# usbFilter.net
KiCad netlist of a schematic drawn in EAGLE
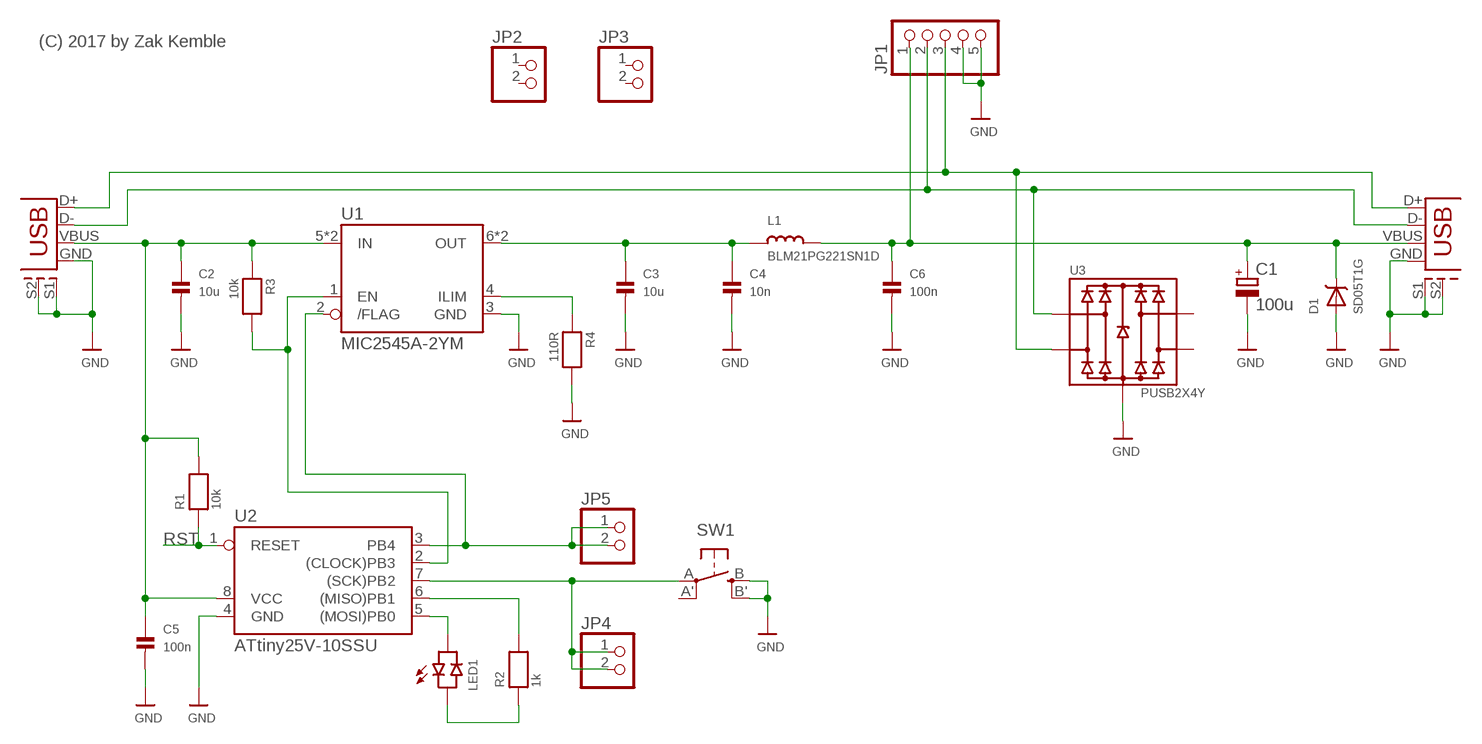
[diagram p0: schematic, sheet 1]

(export (version "E")
  (design (tool "Eeschema 10.0.6"))
  (components
    (comp (ref "C1")
      (value "100u")
      (footprint "eagle-import:E2,5-6")
      (libsource (lib "eagle-import") (part "CPOL-EUE2.5-6"))
    )
    (comp (ref "C2")
      (value "10u")
      (footprint "eagle-import:0805_NO_OUTLINE")
      (libsource (lib "eagle-import") (part "CAP_CERAMIC0805"))
    )
    (comp (ref "C3")
      (value "10u")
      (footprint "eagle-import:0805_NO_OUTLINE")
      (libsource (lib "eagle-import") (part "CAP_CERAMIC0805"))
    )
    (comp (ref "C4")
      (value "10n")
      (footprint "eagle-import:0402")
      (libsource (lib "eagle-import") (part "CAP_CERAMIC0402"))
    )
    (comp (ref "C5")
      (value "100n")
      (footprint "eagle-import:0402")
      (libsource (lib "eagle-import") (part "CAP_CERAMIC0402"))
    )
    (comp (ref "C6")
      (value "100n")
      (footprint "eagle-import:0402")
      (libsource (lib "eagle-import") (part "CAP_CERAMIC0402"))
    )
    (comp (ref "D1")
      (value "SD05T1G")
      (footprint "eagle-import:SOD-323")
      (libsource (lib "eagle-import") (part "DIODE-ZENERSOD-323"))
    )
    (comp (ref "JP1")
      (value "PINHD-1X5")
      (footprint "eagle-import:1X05")
      (libsource (lib "eagle-import") (part "PINHD-1X5"))
    )
    (comp (ref "JP2")
      (value "PINHD-1X2")
      (footprint "eagle-import:1X02")
      (libsource (lib "eagle-import") (part "PINHD-1X2"))
    )
    (comp (ref "JP3")
      (value "PINHD-1X2")
      (footprint "eagle-import:1X02")
      (libsource (lib "eagle-import") (part "PINHD-1X2"))
    )
    (comp (ref "JP4")
      (value "PINHD-1X2")
      (footprint "eagle-import:1X02")
      (libsource (lib "eagle-import") (part "PINHD-1X2"))
    )
    (comp (ref "JP5")
      (value "PINHD-1X2")
      (footprint "eagle-import:1X02")
      (libsource (lib "eagle-import") (part "PINHD-1X2"))
    )
    (comp (ref "L1")
      (value "BLM21PG221SN1D")
      (footprint "eagle-import:0805_NO_OUTLINE")
      (libsource (lib "eagle-import") (part "INDUCTOR0805"))
    )
    (comp (ref "LED1")
      (value "LEDBI0805")
      (footprint "eagle-import:CHIPLED_0805_NOOUTLINE")
      (libsource (lib "eagle-import") (part "LEDBI0805"))
    )
    (comp (ref "R1")
      (value "10k")
      (footprint "eagle-import:0402")
      (libsource (lib "eagle-import") (part "RESISTOR0402"))
    )
    (comp (ref "R2")
      (value "1k")
      (footprint "eagle-import:0402")
      (libsource (lib "eagle-import") (part "RESISTOR0402"))
    )
    (comp (ref "R3")
      (value "10k")
      (footprint "eagle-import:0402")
      (libsource (lib "eagle-import") (part "RESISTOR0402"))
    )
    (comp (ref "R4")
      (value "110R")
      (footprint "eagle-import:0805_NO_OUTLINE")
      (libsource (lib "eagle-import") (part "RESISTOR0805_NO_OUTLINE"))
    )
    (comp (ref "SW1")
      (value "SPST_TACTMC32882")
      (footprint "eagle-import:TACT_SMD4")
      (libsource (lib "eagle-import") (part "SPST_TACTMC32882"))
    )
    (comp (ref "U1")
      (value "MIC2545A-2YM")
      (footprint "eagle-import:SOIC8_150MIL_SMPAD")
      (libsource (lib "eagle-import") (part "NCP380MIC2545"))
    )
    (comp (ref "U2")
      (value "ATtiny25V-10SSU")
      (footprint "eagle-import:SOIC8_150MIL_SMPAD")
      (libsource (lib "eagle-import") (part "ATTINY85150MIL_SMPAD"))
    )
    (comp (ref "U3")
      (value "PUSB2X4Y")
      (footprint "eagle-import:SOT-363")
      (libsource (lib "eagle-import") (part "PUSB2X4Y"))
    )
    (comp (ref "USB1")
      (value "USB-TYPE-B")
      (footprint "eagle-import:USB-TYPE-B")
      (libsource (lib "eagle-import") (part "USB-TYPE-B"))
    )
    (comp (ref "USB2")
      (value "USB-TYPE-A-VERT")
      (footprint "eagle-import:USB-TYPE-A-VERT")
      (libsource (lib "eagle-import") (part "USB-TYPE-A-VERT"))
    )
  )
  (nets
    (net (code "1") (name "/RST") (class "Default")
      (node (ref "R1") (pin "1") (pinfunction "1_1") (pintype "passive"))
      (node (ref "U2") (pin "1") (pinfunction "RESET_1") (pintype "input"))
    )
    (net (code "2") (name "GND") (class "Default")
      (node (ref "C1") (pin "-") (pinfunction "-_-") (pintype "passive"))
      (node (ref "C2") (pin "2") (pinfunction "P$2_2") (pintype "passive"))
      (node (ref "C3") (pin "2") (pinfunction "P$2_2") (pintype "passive"))
      (node (ref "C4") (pin "2") (pinfunction "P$2_2") (pintype "passive"))
      (node (ref "C5") (pin "2") (pinfunction "P$2_2") (pintype "passive"))
      (node (ref "C6") (pin "2") (pinfunction "P$2_2") (pintype "passive"))
      (node (ref "D1") (pin "A") (pinfunction "A_A") (pintype "passive"))
      (node (ref "JP1") (pin "4") (pinfunction "4_4") (pintype "passive"))
      (node (ref "JP1") (pin "5") (pinfunction "5_5") (pintype "passive"))
      (node (ref "R4") (pin "2") (pinfunction "2_2") (pintype "passive"))
      (node (ref "SW1") (pin "B") (pinfunction "S_B") (pintype "passive"))
      (node (ref "SW1") (pin "B'") (pinfunction "S1_B'") (pintype "passive"))
      (node (ref "U1") (pin "3") (pinfunction "GND_3") (pintype "passive"))
      (node (ref "U2") (pin "4") (pinfunction "GND_4") (pintype "power_in"))
      (node (ref "U3") (pin "2") (pinfunction "GND_2") (pintype "passive"))
      (node (ref "USB1") (pin "GND") (pinfunction "GND_GND") (pintype "bidirectional"))
      (node (ref "USB1") (pin "S1") (pinfunction "SHEILD1_S1") (pintype "bidirectional"))
      (node (ref "USB1") (pin "S2") (pinfunction "SHEILD2_S2") (pintype "bidirectional"))
      (node (ref "USB2") (pin "GND") (pinfunction "GND_GND") (pintype "bidirectional"))
      (node (ref "USB2") (pin "S1") (pinfunction "SHEILD1_S1") (pintype "bidirectional"))
      (node (ref "USB2") (pin "S2") (pinfunction "SHEILD2_S2") (pintype "bidirectional"))
    )
    (net (code "3") (name "Net-(C2-P$1)") (class "Default")
      (node (ref "C2") (pin "1") (pinfunction "P$1_1") (pintype "passive"))
      (node (ref "C5") (pin "1") (pinfunction "P$1_1") (pintype "passive"))
      (node (ref "R1") (pin "2") (pinfunction "2_2") (pintype "passive"))
      (node (ref "R3") (pin "1") (pinfunction "1_1") (pintype "passive"))
      (node (ref "U1") (pin "5") (pinfunction "IN_5") (pintype "passive"))
      (node (ref "U1") (pin "7") (pinfunction "IN_7") (pintype "passive"))
      (node (ref "U2") (pin "8") (pinfunction "VCC_8") (pintype "power_in"))
      (node (ref "USB1") (pin "VBUS") (pinfunction "VBUS_VBUS") (pintype "bidirectional"))
    )
    (net (code "4") (name "Net-(C3-P$1)") (class "Default")
      (node (ref "C3") (pin "1") (pinfunction "P$1_1") (pintype "passive"))
      (node (ref "C4") (pin "1") (pinfunction "P$1_1") (pintype "passive"))
      (node (ref "L1") (pin "1") (pinfunction "1_1") (pintype "passive"))
      (node (ref "U1") (pin "6") (pinfunction "OUT_6") (pintype "passive"))
      (node (ref "U1") (pin "8") (pinfunction "OUT_8") (pintype "passive"))
    )
    (net (code "5") (name "Net-(C6-P$1)") (class "Default")
      (node (ref "C1") (pin "+") (pinfunction "+_+") (pintype "passive"))
      (node (ref "C6") (pin "1") (pinfunction "P$1_1") (pintype "passive"))
      (node (ref "D1") (pin "C") (pinfunction "C_C") (pintype "passive"))
      (node (ref "JP1") (pin "1") (pinfunction "1_1") (pintype "passive"))
      (node (ref "L1") (pin "2") (pinfunction "2_2") (pintype "passive"))
      (node (ref "USB2") (pin "VBUS") (pinfunction "VBUS_VBUS") (pintype "bidirectional"))
    )
    (net (code "6") (name "Net-(LED1-PadC)") (class "Default")
      (node (ref "LED1") (pin "C") (pinfunction "C_C") (pintype "passive"))
      (node (ref "R2") (pin "1") (pinfunction "1_1") (pintype "passive"))
    )
    (net (code "7") (name "Net-(SW1-P)") (class "Default")
      (node (ref "JP4") (pin "1") (pinfunction "1_1") (pintype "passive"))
      (node (ref "JP4") (pin "2") (pinfunction "2_2") (pintype "passive"))
      (node (ref "SW1") (pin "A") (pinfunction "P_A") (pintype "passive"))
      (node (ref "U2") (pin "7") (pinfunction "(SCK)PB2_7") (pintype "bidirectional"))
    )
    (net (code "8") (name "Net-(U1-EN)") (class "Default")
      (node (ref "R3") (pin "2") (pinfunction "2_2") (pintype "passive"))
      (node (ref "U1") (pin "1") (pinfunction "EN_1") (pintype "passive"))
      (node (ref "U2") (pin "2") (pinfunction "(CLOCK)PB3_2") (pintype "bidirectional"))
    )
    (net (code "9") (name "Net-(U1-ILIM)") (class "Default")
      (node (ref "R4") (pin "1") (pinfunction "1_1") (pintype "passive"))
      (node (ref "U1") (pin "4") (pinfunction "ILIM_4") (pintype "passive"))
    )
    (net (code "10") (name "Net-(U1-{slash}FLAG)") (class "Default")
      (node (ref "JP5") (pin "1") (pinfunction "1_1") (pintype "passive"))
      (node (ref "JP5") (pin "2") (pinfunction "2_2") (pintype "passive"))
      (node (ref "U1") (pin "2") (pinfunction "/FLAG_2") (pintype "input"))
      (node (ref "U2") (pin "3") (pinfunction "PB4_3") (pintype "bidirectional"))
    )
    (net (code "11") (name "Net-(U2-(MISO)PB1)") (class "Default")
      (node (ref "R2") (pin "2") (pinfunction "2_2") (pintype "passive"))
      (node (ref "U2") (pin "6") (pinfunction "(MISO)PB1_6") (pintype "bidirectional"))
    )
    (net (code "12") (name "Net-(U2-(MOSI)PB0)") (class "Default")
      (node (ref "LED1") (pin "A") (pinfunction "A_A") (pintype "passive"))
      (node (ref "U2") (pin "5") (pinfunction "(MOSI)PB0_5") (pintype "bidirectional"))
    )
    (net (code "13") (name "Net-(U3-IO1)") (class "Default")
      (node (ref "JP1") (pin "2") (pinfunction "2_2") (pintype "passive"))
      (node (ref "U3") (pin "1") (pinfunction "IO1_1") (pintype "passive"))
      (node (ref "USB1") (pin "D-") (pinfunction "D-_D-") (pintype "bidirectional"))
      (node (ref "USB2") (pin "D-") (pinfunction "D-_D-") (pintype "bidirectional"))
    )
    (net (code "14") (name "Net-(U3-IO2)") (class "Default")
      (node (ref "JP1") (pin "3") (pinfunction "3_3") (pintype "passive"))
      (node (ref "U3") (pin "3") (pinfunction "IO2_3") (pintype "passive"))
      (node (ref "USB1") (pin "D+") (pinfunction "D+_D+") (pintype "bidirectional"))
      (node (ref "USB2") (pin "D+") (pinfunction "D+_D+") (pintype "bidirectional"))
    )
    (net (code "15") (name "unconnected-(JP2-Pad1)") (class "Default")
      (node (ref "JP2") (pin "1") (pinfunction "1_1") (pintype "passive"))
    )
    (net (code "16") (name "unconnected-(JP2-Pad2)") (class "Default")
      (node (ref "JP2") (pin "2") (pinfunction "2_2") (pintype "passive"))
    )
    (net (code "17") (name "unconnected-(JP3-Pad1)") (class "Default")
      (node (ref "JP3") (pin "1") (pinfunction "1_1") (pintype "passive"))
    )
    (net (code "18") (name "unconnected-(JP3-Pad2)") (class "Default")
      (node (ref "JP3") (pin "2") (pinfunction "2_2") (pintype "passive"))
    )
    (net (code "19") (name "unconnected-(SW1-P1-PadA')") (class "Default")
      (node (ref "SW1") (pin "A'") (pinfunction "P1_A'") (pintype "passive"))
    )
    (net (code "20") (name "unconnected-(U3-IO3-Pad4)") (class "Default")
      (node (ref "U3") (pin "4") (pinfunction "IO3_4") (pintype "passive"))
    )
    (net (code "21") (name "unconnected-(U3-IO4-Pad6)") (class "Default")
      (node (ref "U3") (pin "6") (pinfunction "IO4_6") (pintype "passive"))
    )
  )
)
